# C717469.net
KiCad netlist of a schematic drawn in EAGLE
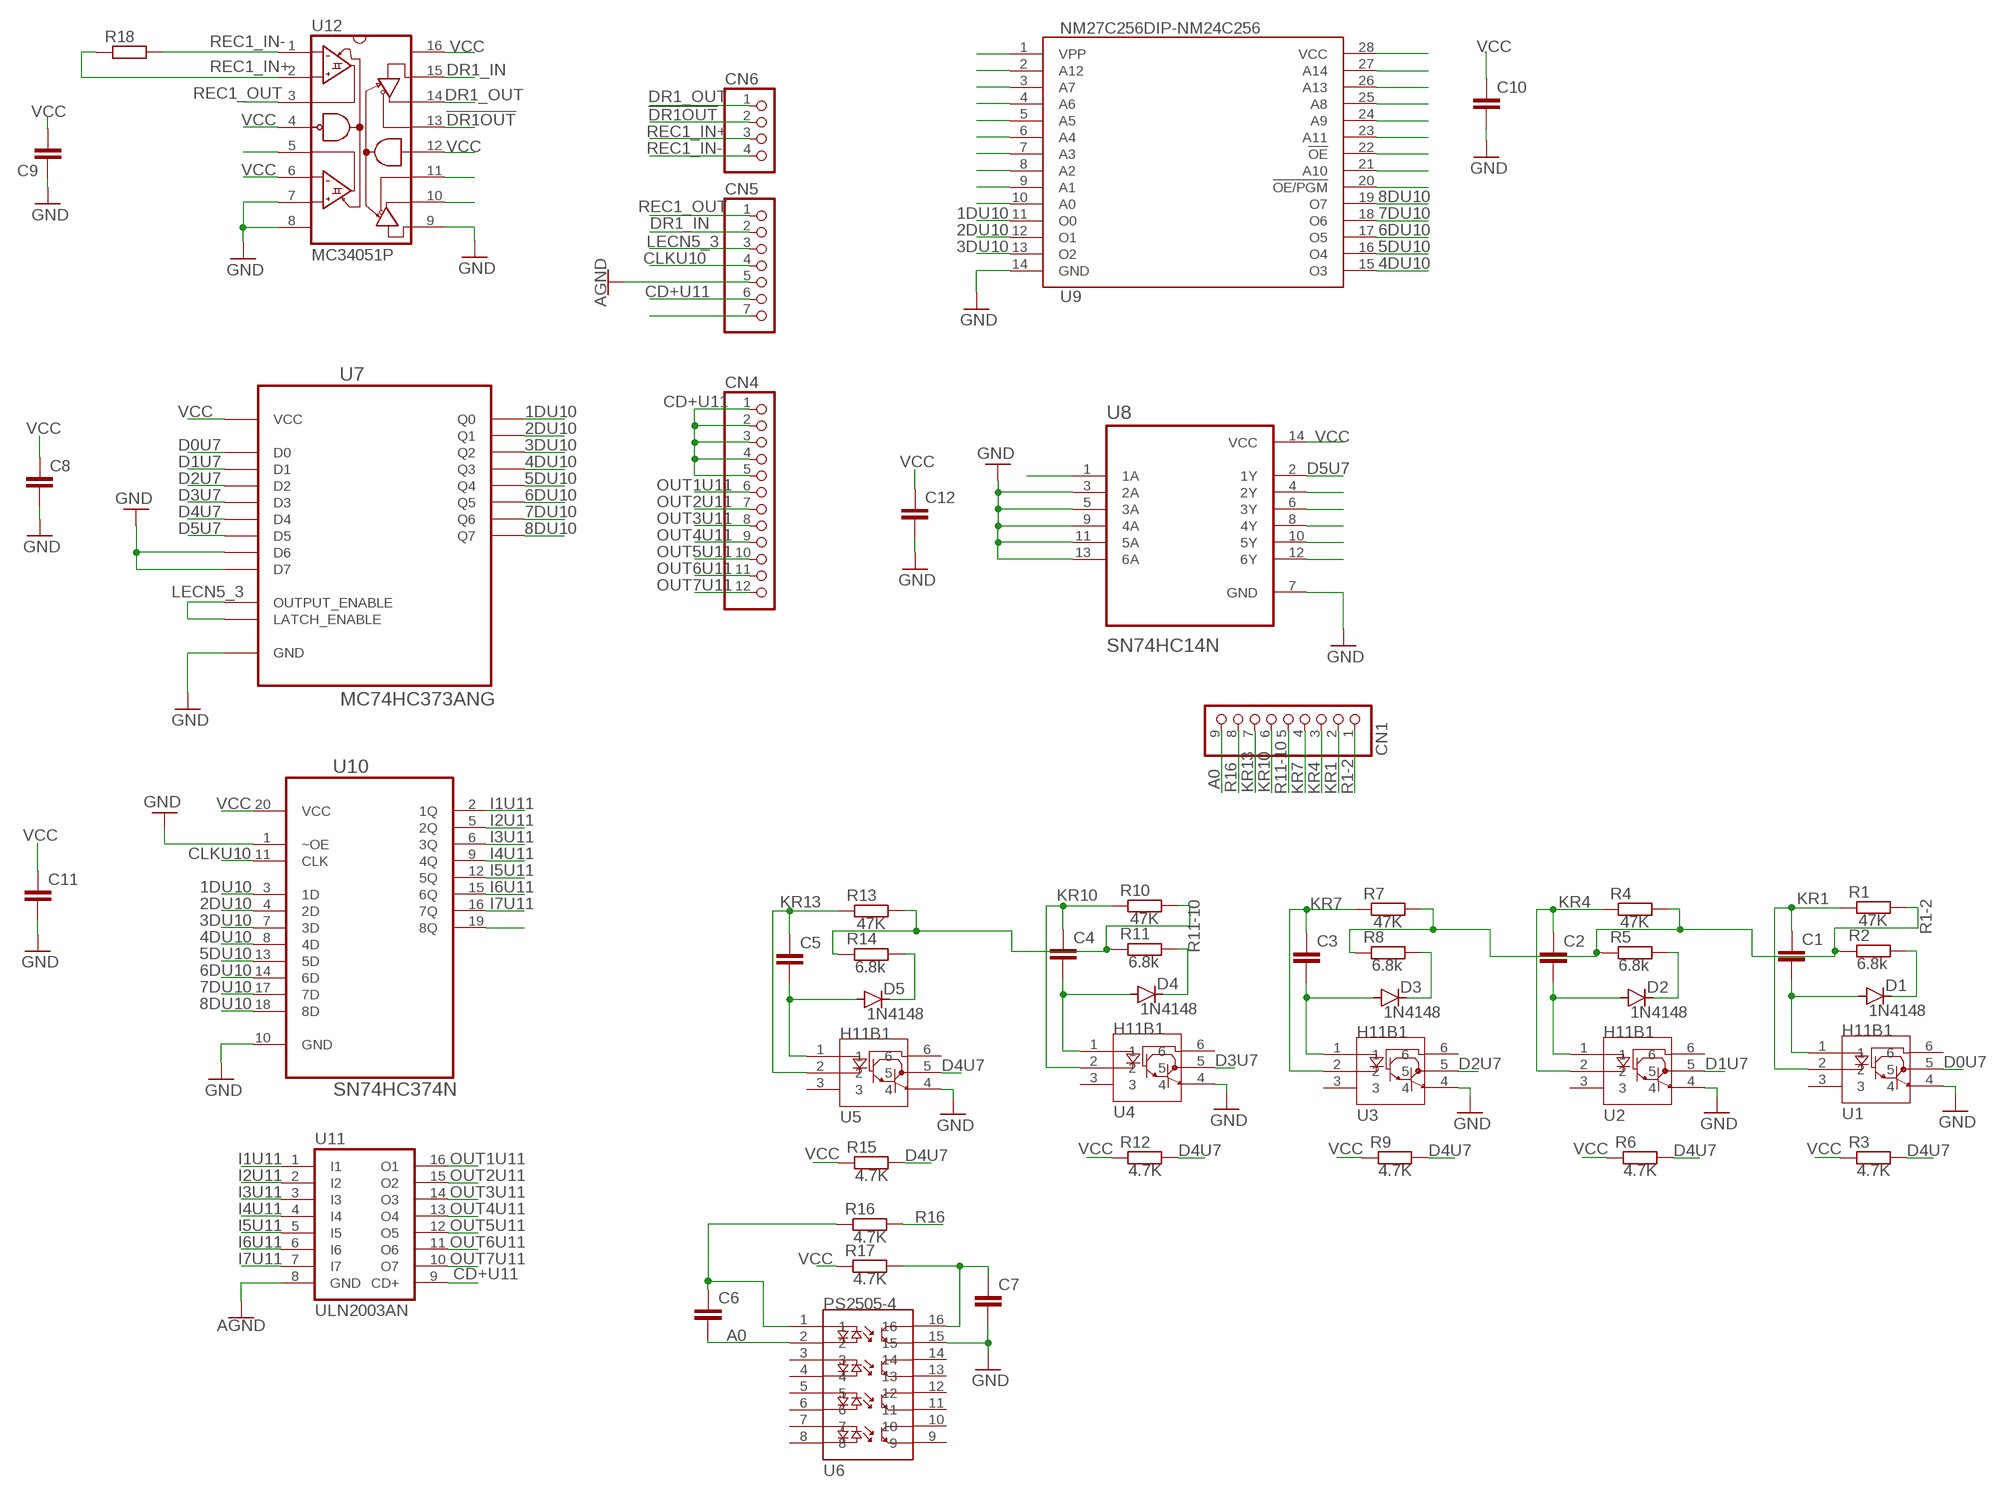
[diagram p0: schematic, sheet 1]

(export (version "E")
  (design (tool "Eeschema 10.0.6"))
  (components
    (comp (ref "C1")
      (value "C-EU025-025X050")
      (footprint "eagle-import:C025-025X050")
      (libsource (lib "eagle-import") (part "C-EU025-025X050"))
    )
    (comp (ref "C2")
      (value "C-EU025-025X050")
      (footprint "eagle-import:C025-025X050")
      (libsource (lib "eagle-import") (part "C-EU025-025X050"))
    )
    (comp (ref "C3")
      (value "C-EU025-025X050")
      (footprint "eagle-import:C025-025X050")
      (libsource (lib "eagle-import") (part "C-EU025-025X050"))
    )
    (comp (ref "C4")
      (value "C-EU025-025X050")
      (footprint "eagle-import:C025-025X050")
      (libsource (lib "eagle-import") (part "C-EU025-025X050"))
    )
    (comp (ref "C5")
      (value "C-EU025-025X050")
      (footprint "eagle-import:C025-025X050")
      (libsource (lib "eagle-import") (part "C-EU025-025X050"))
    )
    (comp (ref "C6")
      (value "C-EU025-025X050")
      (footprint "eagle-import:C025-025X050")
      (libsource (lib "eagle-import") (part "C-EU025-025X050"))
    )
    (comp (ref "C7")
      (value "C-EU025-025X050")
      (footprint "eagle-import:C025-025X050")
      (libsource (lib "eagle-import") (part "C-EU025-025X050"))
    )
    (comp (ref "C8")
      (value "C-EU025-025X050")
      (footprint "eagle-import:C025-025X050")
      (libsource (lib "eagle-import") (part "C-EU025-025X050"))
    )
    (comp (ref "C9")
      (value "C-EU025-025X050")
      (footprint "eagle-import:C025-025X050")
      (libsource (lib "eagle-import") (part "C-EU025-025X050"))
    )
    (comp (ref "C10")
      (value "C-EU025-025X050")
      (footprint "eagle-import:C025-025X050")
      (libsource (lib "eagle-import") (part "C-EU025-025X050"))
    )
    (comp (ref "C11")
      (value "C-EU025-025X050")
      (footprint "eagle-import:C025-025X050")
      (libsource (lib "eagle-import") (part "C-EU025-025X050"))
    )
    (comp (ref "C12")
      (value "C-EU025-025X050")
      (footprint "eagle-import:C025-025X050")
      (libsource (lib "eagle-import") (part "C-EU025-025X050"))
    )
    (comp (ref "CN1")
      (value "PINHD-1X9")
      (footprint "eagle-import:1X09")
      (libsource (lib "eagle-import") (part "PINHD-1X9"))
    )
    (comp (ref "CN4")
      (value "PINHD-1X12")
      (footprint "eagle-import:1X12")
      (libsource (lib "eagle-import") (part "PINHD-1X12"))
    )
    (comp (ref "CN5")
      (value "PINHD-1X7")
      (footprint "eagle-import:1X07")
      (libsource (lib "eagle-import") (part "PINHD-1X7"))
    )
    (comp (ref "CN6")
      (value "PINHD-1X4")
      (footprint "eagle-import:1X04")
      (libsource (lib "eagle-import") (part "PINHD-1X4"))
    )
    (comp (ref "D1")
      (value "1N4148")
      (footprint "eagle-import:DO35-10")
      (libsource (lib "eagle-import") (part "1N4148DO35-10"))
    )
    (comp (ref "D2")
      (value "1N4148")
      (footprint "eagle-import:DO35-10")
      (libsource (lib "eagle-import") (part "1N4148DO35-10"))
    )
    (comp (ref "D3")
      (value "1N4148")
      (footprint "eagle-import:DO35-10")
      (libsource (lib "eagle-import") (part "1N4148DO35-10"))
    )
    (comp (ref "D4")
      (value "1N4148")
      (footprint "eagle-import:DO35-10")
      (libsource (lib "eagle-import") (part "1N4148DO35-10"))
    )
    (comp (ref "D5")
      (value "1N4148")
      (footprint "eagle-import:DO35-10")
      (libsource (lib "eagle-import") (part "1N4148DO35-10"))
    )
    (comp (ref "R1")
      (value "47K")
      (footprint "eagle-import:0207_10")
      (libsource (lib "eagle-import") (part "R-EU_0207/10"))
    )
    (comp (ref "R2")
      (value "6.8k")
      (footprint "eagle-import:0207_10")
      (libsource (lib "eagle-import") (part "R-EU_0207/10"))
    )
    (comp (ref "R3")
      (value "4.7K")
      (footprint "eagle-import:0207_10")
      (libsource (lib "eagle-import") (part "R-EU_0207/10"))
    )
    (comp (ref "R4")
      (value "47K")
      (footprint "eagle-import:0207_10")
      (libsource (lib "eagle-import") (part "R-EU_0207/10"))
    )
    (comp (ref "R5")
      (value "6.8k")
      (footprint "eagle-import:0207_10")
      (libsource (lib "eagle-import") (part "R-EU_0207/10"))
    )
    (comp (ref "R6")
      (value "4.7K")
      (footprint "eagle-import:0207_10")
      (libsource (lib "eagle-import") (part "R-EU_0207/10"))
    )
    (comp (ref "R7")
      (value "47K")
      (footprint "eagle-import:0207_10")
      (libsource (lib "eagle-import") (part "R-EU_0207/10"))
    )
    (comp (ref "R8")
      (value "6.8k")
      (footprint "eagle-import:0207_10")
      (libsource (lib "eagle-import") (part "R-EU_0207/10"))
    )
    (comp (ref "R9")
      (value "4.7K")
      (footprint "eagle-import:0207_10")
      (libsource (lib "eagle-import") (part "R-EU_0207/10"))
    )
    (comp (ref "R10")
      (value "47K")
      (footprint "eagle-import:0207_10")
      (libsource (lib "eagle-import") (part "R-EU_0207/10"))
    )
    (comp (ref "R11")
      (value "6.8k")
      (footprint "eagle-import:0207_10")
      (libsource (lib "eagle-import") (part "R-EU_0207/10"))
    )
    (comp (ref "R12")
      (value "4.7K")
      (footprint "eagle-import:0207_10")
      (libsource (lib "eagle-import") (part "R-EU_0207/10"))
    )
    (comp (ref "R13")
      (value "47K")
      (footprint "eagle-import:0207_10")
      (libsource (lib "eagle-import") (part "R-EU_0207/10"))
    )
    (comp (ref "R14")
      (value "6.8k")
      (footprint "eagle-import:0207_10")
      (libsource (lib "eagle-import") (part "R-EU_0207/10"))
    )
    (comp (ref "R15")
      (value "4.7K")
      (footprint "eagle-import:0207_10")
      (libsource (lib "eagle-import") (part "R-EU_0207/10"))
    )
    (comp (ref "R16")
      (value "4.7K")
      (footprint "eagle-import:0207_10")
      (libsource (lib "eagle-import") (part "R-EU_0207/10"))
    )
    (comp (ref "R17")
      (value "4.7K")
      (footprint "eagle-import:0207_10")
      (libsource (lib "eagle-import") (part "R-EU_0207/10"))
    )
    (comp (ref "R18")
      (value "R-EU_0207/10")
      (footprint "eagle-import:0207_10")
      (libsource (lib "eagle-import") (part "R-EU_0207/10"))
    )
    (comp (ref "U1")
      (value "H11B1")
      (footprint "eagle-import:DIP762W50P254L730H410Q6")
      (libsource (lib "eagle-import") (part "H11B1DIP6"))
    )
    (comp (ref "U2")
      (value "H11B1")
      (footprint "eagle-import:DIP762W50P254L730H410Q6")
      (libsource (lib "eagle-import") (part "H11B1DIP6"))
    )
    (comp (ref "U3")
      (value "H11B1")
      (footprint "eagle-import:DIP762W50P254L730H410Q6")
      (libsource (lib "eagle-import") (part "H11B1DIP6"))
    )
    (comp (ref "U4")
      (value "H11B1")
      (footprint "eagle-import:DIP762W50P254L730H410Q6")
      (libsource (lib "eagle-import") (part "H11B1DIP6"))
    )
    (comp (ref "U5")
      (value "H11B1")
      (footprint "eagle-import:DIP762W50P254L730H410Q6")
      (libsource (lib "eagle-import") (part "H11B1DIP6"))
    )
    (comp (ref "U6")
      (value "PS2505-4")
      (footprint "eagle-import:D16-L")
      (libsource (lib "eagle-import") (part "PS2505-4"))
    )
    (comp (ref "U7")
      (value "MC74HC373ANG")
      (footprint "eagle-import:DIP254P762X457-20")
      (fields (field (name "MF") "ON Semiconductor"))
      (libsource (lib "eagle-import") (part "MC74HC373ANG"))
    )
    (comp (ref "U8")
      (value "SN74HC14N")
      (footprint "eagle-import:DIP794W45P254L1969H508Q14")
      (fields (field (name "MF") "Texas Instruments"))
      (libsource (lib "eagle-import") (part "SN74HC14N"))
    )
    (comp (ref "U9")
      (value "NM27C256DIP-NM24C256")
      (footprint "eagle-import:DIP1499W48P254L3734H572Q28")
      (libsource (lib "eagle-import") (part "NM27C256DIP-NM24C256"))
    )
    (comp (ref "U10")
      (value "SN74HC374N")
      (footprint "eagle-import:DIP254P762X508-20")
      (fields (field (name "MF") "Texas Instruments"))
      (libsource (lib "eagle-import") (part "SN74HC374N"))
    )
    (comp (ref "U11")
      (value "ULN2003AN")
      (footprint "eagle-import:DIL16")
      (libsource (lib "eagle-import") (part "ULN2003AN"))
    )
    (comp (ref "U12")
      (value "MC34051P")
      (footprint "eagle-import:D16")
      (libsource (lib "eagle-import") (part "MC34051P"))
    )
  )
  (nets
    (net (code "1") (name "/1DU10") (class "Default")
      (node (ref "U10") (pin "3") (pinfunction "1D_3") (pintype "input"))
      (node (ref "U7") (pin "2") (pinfunction "Q0_2") (pintype "output"))
      (node (ref "U9") (pin "11") (pinfunction "O0_11") (pintype "bidirectional"))
    )
    (net (code "2") (name "/2DU10") (class "Default")
      (node (ref "U10") (pin "4") (pinfunction "2D_4") (pintype "input"))
      (node (ref "U7") (pin "5") (pinfunction "Q1_5") (pintype "output"))
      (node (ref "U9") (pin "12") (pinfunction "O1_12") (pintype "bidirectional"))
    )
    (net (code "3") (name "/3DU10") (class "Default")
      (node (ref "U10") (pin "7") (pinfunction "3D_7") (pintype "input"))
      (node (ref "U7") (pin "6") (pinfunction "Q2_6") (pintype "output"))
      (node (ref "U9") (pin "13") (pinfunction "O2_13") (pintype "bidirectional"))
    )
    (net (code "4") (name "/4DU10") (class "Default")
      (node (ref "U10") (pin "8") (pinfunction "4D_8") (pintype "input"))
      (node (ref "U7") (pin "9") (pinfunction "Q3_9") (pintype "output"))
      (node (ref "U9") (pin "15") (pinfunction "O3_15") (pintype "bidirectional"))
    )
    (net (code "5") (name "/5DU10") (class "Default")
      (node (ref "U10") (pin "13") (pinfunction "5D_13") (pintype "input"))
      (node (ref "U7") (pin "12") (pinfunction "Q4_12") (pintype "output"))
      (node (ref "U9") (pin "16") (pinfunction "O4_16") (pintype "bidirectional"))
    )
    (net (code "6") (name "/6DU10") (class "Default")
      (node (ref "U10") (pin "14") (pinfunction "6D_14") (pintype "input"))
      (node (ref "U7") (pin "15") (pinfunction "Q5_15") (pintype "output"))
      (node (ref "U9") (pin "17") (pinfunction "O5_17") (pintype "bidirectional"))
    )
    (net (code "7") (name "/7DU10") (class "Default")
      (node (ref "U10") (pin "17") (pinfunction "7D_17") (pintype "input"))
      (node (ref "U7") (pin "16") (pinfunction "Q6_16") (pintype "output"))
      (node (ref "U9") (pin "18") (pinfunction "O6_18") (pintype "bidirectional"))
    )
    (net (code "8") (name "/8DU10") (class "Default")
      (node (ref "U10") (pin "18") (pinfunction "8D_18") (pintype "input"))
      (node (ref "U7") (pin "19") (pinfunction "Q7_19") (pintype "output"))
      (node (ref "U9") (pin "19") (pinfunction "O7_19") (pintype "bidirectional"))
    )
    (net (code "9") (name "/A0") (class "Default")
      (node (ref "C6") (pin "2") (pinfunction "2_2") (pintype "passive"))
      (node (ref "CN1") (pin "9") (pinfunction "9_9") (pintype "passive"))
      (node (ref "U6") (pin "2") (pinfunction "2_2") (pintype "bidirectional"))
    )
    (net (code "10") (name "/CD+U11") (class "Default")
      (node (ref "CN4") (pin "1") (pinfunction "1_1") (pintype "passive"))
      (node (ref "CN4") (pin "2") (pinfunction "2_2") (pintype "passive"))
      (node (ref "CN4") (pin "3") (pinfunction "3_3") (pintype "passive"))
      (node (ref "CN4") (pin "4") (pinfunction "4_4") (pintype "passive"))
      (node (ref "CN4") (pin "5") (pinfunction "5_5") (pintype "passive"))
      (node (ref "CN5") (pin "6") (pinfunction "6_6") (pintype "passive"))
      (node (ref "U11") (pin "9") (pinfunction "CD+_9") (pintype "passive"))
    )
    (net (code "11") (name "/CLKU10") (class "Default")
      (node (ref "CN5") (pin "4") (pinfunction "4_4") (pintype "passive"))
      (node (ref "U10") (pin "11") (pinfunction "CLK_11") (pintype "input"))
    )
    (net (code "12") (name "/D0U7") (class "Default")
      (node (ref "U1") (pin "5") (pinfunction "5_5") (pintype "bidirectional"))
      (node (ref "U7") (pin "3") (pinfunction "D0_3") (pintype "input"))
    )
    (net (code "13") (name "/D1U7") (class "Default")
      (node (ref "U2") (pin "5") (pinfunction "5_5") (pintype "bidirectional"))
      (node (ref "U7") (pin "4") (pinfunction "D1_4") (pintype "input"))
    )
    (net (code "14") (name "/D2U7") (class "Default")
      (node (ref "U3") (pin "5") (pinfunction "5_5") (pintype "bidirectional"))
      (node (ref "U7") (pin "7") (pinfunction "D2_7") (pintype "input"))
    )
    (net (code "15") (name "/D3U7") (class "Default")
      (node (ref "U4") (pin "5") (pinfunction "5_5") (pintype "bidirectional"))
      (node (ref "U7") (pin "8") (pinfunction "D3_8") (pintype "input"))
    )
    (net (code "16") (name "/D4U7") (class "Default")
      (node (ref "R12") (pin "2") (pinfunction "2_2") (pintype "passive"))
      (node (ref "R15") (pin "2") (pinfunction "2_2") (pintype "passive"))
      (node (ref "R3") (pin "2") (pinfunction "2_2") (pintype "passive"))
      (node (ref "R6") (pin "2") (pinfunction "2_2") (pintype "passive"))
      (node (ref "R9") (pin "2") (pinfunction "2_2") (pintype "passive"))
      (node (ref "U5") (pin "5") (pinfunction "5_5") (pintype "bidirectional"))
      (node (ref "U7") (pin "13") (pinfunction "D4_13") (pintype "input"))
    )
    (net (code "17") (name "/D5U7") (class "Default")
      (node (ref "U7") (pin "14") (pinfunction "D5_14") (pintype "input"))
      (node (ref "U8") (pin "2") (pinfunction "1Y_2") (pintype "output"))
    )
    (net (code "18") (name "/DR1_IN") (class "Default")
      (node (ref "CN5") (pin "2") (pinfunction "2_2") (pintype "passive"))
      (node (ref "U12") (pin "15") (pinfunction "DR1IN_15") (pintype "bidirectional"))
    )
    (net (code "19") (name "/DR1_OUT") (class "Default")
      (node (ref "CN6") (pin "1") (pinfunction "1_1") (pintype "passive"))
      (node (ref "U12") (pin "14") (pinfunction "DR1OUT_14") (pintype "bidirectional"))
    )
    (net (code "20") (name "/I1U11") (class "Default")
      (node (ref "U10") (pin "2") (pinfunction "1Q_2") (pintype "output"))
      (node (ref "U11") (pin "1") (pinfunction "I1_1") (pintype "input"))
    )
    (net (code "21") (name "/I2U11") (class "Default")
      (node (ref "U10") (pin "5") (pinfunction "2Q_5") (pintype "output"))
      (node (ref "U11") (pin "2") (pinfunction "I2_2") (pintype "input"))
    )
    (net (code "22") (name "/I3U11") (class "Default")
      (node (ref "U10") (pin "6") (pinfunction "3Q_6") (pintype "output"))
      (node (ref "U11") (pin "3") (pinfunction "I3_3") (pintype "input"))
    )
    (net (code "23") (name "/I4U11") (class "Default")
      (node (ref "U10") (pin "9") (pinfunction "4Q_9") (pintype "output"))
      (node (ref "U11") (pin "4") (pinfunction "I4_4") (pintype "input"))
    )
    (net (code "24") (name "/I5U11") (class "Default")
      (node (ref "U10") (pin "12") (pinfunction "5Q_12") (pintype "output"))
      (node (ref "U11") (pin "5") (pinfunction "I5_5") (pintype "input"))
    )
    (net (code "25") (name "/I6U11") (class "Default")
      (node (ref "U10") (pin "15") (pinfunction "6Q_15") (pintype "output"))
      (node (ref "U11") (pin "6") (pinfunction "I6_6") (pintype "input"))
    )
    (net (code "26") (name "/I7U11") (class "Default")
      (node (ref "U10") (pin "16") (pinfunction "7Q_16") (pintype "output"))
      (node (ref "U11") (pin "7") (pinfunction "I7_7") (pintype "input"))
    )
    (net (code "27") (name "/KR1") (class "Default")
      (node (ref "C1") (pin "1") (pinfunction "1_1") (pintype "passive"))
      (node (ref "CN1") (pin "2") (pinfunction "2_2") (pintype "passive"))
      (node (ref "R1") (pin "1") (pinfunction "1_1") (pintype "passive"))
      (node (ref "U1") (pin "2") (pinfunction "2_2") (pintype "bidirectional"))
    )
    (net (code "28") (name "/KR4") (class "Default")
      (node (ref "C2") (pin "1") (pinfunction "1_1") (pintype "passive"))
      (node (ref "CN1") (pin "3") (pinfunction "3_3") (pintype "passive"))
      (node (ref "R4") (pin "1") (pinfunction "1_1") (pintype "passive"))
      (node (ref "U2") (pin "2") (pinfunction "2_2") (pintype "bidirectional"))
    )
    (net (code "29") (name "/KR7") (class "Default")
      (node (ref "C3") (pin "1") (pinfunction "1_1") (pintype "passive"))
      (node (ref "CN1") (pin "4") (pinfunction "4_4") (pintype "passive"))
      (node (ref "R7") (pin "1") (pinfunction "1_1") (pintype "passive"))
      (node (ref "U3") (pin "2") (pinfunction "2_2") (pintype "bidirectional"))
    )
    (net (code "30") (name "/KR10") (class "Default")
      (node (ref "C4") (pin "1") (pinfunction "1_1") (pintype "passive"))
      (node (ref "CN1") (pin "6") (pinfunction "6_6") (pintype "passive"))
      (node (ref "R10") (pin "1") (pinfunction "1_1") (pintype "passive"))
      (node (ref "U4") (pin "2") (pinfunction "2_2") (pintype "bidirectional"))
    )
    (net (code "31") (name "/KR13") (class "Default")
      (node (ref "C5") (pin "1") (pinfunction "1_1") (pintype "passive"))
      (node (ref "CN1") (pin "7") (pinfunction "7_7") (pintype "passive"))
      (node (ref "R13") (pin "1") (pinfunction "1_1") (pintype "passive"))
      (node (ref "U5") (pin "2") (pinfunction "2_2") (pintype "bidirectional"))
    )
    (net (code "32") (name "/LECN5_3") (class "Default")
      (node (ref "CN5") (pin "3") (pinfunction "3_3") (pintype "passive"))
      (node (ref "U7") (pin "1") (pinfunction "OUTPUT_ENABLE_1") (pintype "input"))
      (node (ref "U7") (pin "11") (pinfunction "LATCH_ENABLE_11") (pintype "input"))
    )
    (net (code "33") (name "/OUT1U11") (class "Default")
      (node (ref "CN4") (pin "6") (pinfunction "6_6") (pintype "passive"))
      (node (ref "U11") (pin "16") (pinfunction "O1_16") (pintype "open_collector"))
    )
    (net (code "34") (name "/OUT2U11") (class "Default")
      (node (ref "CN4") (pin "7") (pinfunction "7_7") (pintype "passive"))
      (node (ref "U11") (pin "15") (pinfunction "O2_15") (pintype "open_collector"))
    )
    (net (code "35") (name "/OUT3U11") (class "Default")
      (node (ref "CN4") (pin "8") (pinfunction "8_8") (pintype "passive"))
      (node (ref "U11") (pin "14") (pinfunction "O3_14") (pintype "open_collector"))
    )
    (net (code "36") (name "/OUT4U11") (class "Default")
      (node (ref "CN4") (pin "9") (pinfunction "9_9") (pintype "passive"))
      (node (ref "U11") (pin "13") (pinfunction "O4_13") (pintype "open_collector"))
    )
    (net (code "37") (name "/OUT5U11") (class "Default")
      (node (ref "CN4") (pin "10") (pinfunction "10_10") (pintype "passive"))
      (node (ref "U11") (pin "12") (pinfunction "O5_12") (pintype "open_collector"))
    )
    (net (code "38") (name "/OUT6U11") (class "Default")
      (node (ref "CN4") (pin "11") (pinfunction "11_11") (pintype "passive"))
      (node (ref "U11") (pin "11") (pinfunction "O6_11") (pintype "open_collector"))
    )
    (net (code "39") (name "/OUT7U11") (class "Default")
      (node (ref "CN4") (pin "12") (pinfunction "12_12") (pintype "passive"))
      (node (ref "U11") (pin "10") (pinfunction "O7_10") (pintype "open_collector"))
    )
    (net (code "40") (name "/R1-2") (class "Default")
      (node (ref "CN1") (pin "1") (pinfunction "1_1") (pintype "passive"))
      (node (ref "R1") (pin "2") (pinfunction "2_2") (pintype "passive"))
      (node (ref "R2") (pin "1") (pinfunction "1_1") (pintype "passive"))
      (node (ref "R4") (pin "2") (pinfunction "2_2") (pintype "passive"))
      (node (ref "R5") (pin "1") (pinfunction "1_1") (pintype "passive"))
      (node (ref "R7") (pin "2") (pinfunction "2_2") (pintype "passive"))
      (node (ref "R8") (pin "1") (pinfunction "1_1") (pintype "passive"))
    )
    (net (code "41") (name "/R11-10") (class "Default")
      (node (ref "CN1") (pin "5") (pinfunction "5_5") (pintype "passive"))
      (node (ref "R10") (pin "2") (pinfunction "2_2") (pintype "passive"))
      (node (ref "R11") (pin "1") (pinfunction "1_1") (pintype "passive"))
      (node (ref "R13") (pin "2") (pinfunction "2_2") (pintype "passive"))
      (node (ref "R14") (pin "1") (pinfunction "1_1") (pintype "passive"))
    )
    (net (code "42") (name "/R16") (class "Default")
      (node (ref "CN1") (pin "8") (pinfunction "8_8") (pintype "passive"))
      (node (ref "R16") (pin "2") (pinfunction "2_2") (pintype "passive"))
    )
    (net (code "43") (name "/REC1_IN+") (class "Default")
      (node (ref "CN6") (pin "3") (pinfunction "3_3") (pintype "passive"))
      (node (ref "R18") (pin "1") (pinfunction "1_1") (pintype "passive"))
      (node (ref "U12") (pin "2") (pinfunction "REC1+IN_2") (pintype "bidirectional"))
    )
    (net (code "44") (name "/REC1_IN-") (class "Default")
      (node (ref "CN6") (pin "4") (pinfunction "4_4") (pintype "passive"))
      (node (ref "R18") (pin "2") (pinfunction "2_2") (pintype "passive"))
      (node (ref "U12") (pin "1") (pinfunction "REC1-IN_1") (pintype "bidirectional"))
    )
    (net (code "45") (name "/REC1_OUT") (class "Default")
      (node (ref "CN5") (pin "1") (pinfunction "1_1") (pintype "passive"))
      (node (ref "U12") (pin "3") (pinfunction "REC1OUT_3") (pintype "bidirectional"))
    )
    (net (code "46") (name "/VCC") (class "Default")
      (node (ref "C10") (pin "1") (pinfunction "1_1") (pintype "passive"))
      (node (ref "C11") (pin "1") (pinfunction "1_1") (pintype "passive"))
      (node (ref "C12") (pin "1") (pinfunction "1_1") (pintype "passive"))
      (node (ref "C8") (pin "1") (pinfunction "1_1") (pintype "passive"))
      (node (ref "C9") (pin "2") (pinfunction "2_2") (pintype "passive"))
      (node (ref "R12") (pin "1") (pinfunction "1_1") (pintype "passive"))
      (node (ref "R15") (pin "1") (pinfunction "1_1") (pintype "passive"))
      (node (ref "R17") (pin "1") (pinfunction "1_1") (pintype "passive"))
      (node (ref "R3") (pin "1") (pinfunction "1_1") (pintype "passive"))
      (node (ref "R6") (pin "1") (pinfunction "1_1") (pintype "passive"))
      (node (ref "R9") (pin "1") (pinfunction "1_1") (pintype "passive"))
      (node (ref "U10") (pin "20") (pinfunction "VCC_20") (pintype "power_in"))
      (node (ref "U12") (pin "12") (pinfunction "DREN_12") (pintype "bidirectional"))
      (node (ref "U12") (pin "16") (pinfunction "VCC_16") (pintype "bidirectional"))
      (node (ref "U12") (pin "4") (pinfunction "~{RECEN}_4") (pintype "bidirectional"))
      (node (ref "U12") (pin "6") (pinfunction "REC2+IN_6") (pintype "bidirectional"))
      (node (ref "U7") (pin "20") (pinfunction "VCC_20") (pintype "power_in"))
      (node (ref "U8") (pin "14") (pinfunction "VCC_14") (pintype "power_in"))
    )
    (net (code "47") (name "/~{DR1OUT}") (class "Default")
      (node (ref "CN6") (pin "2") (pinfunction "2_2") (pintype "passive"))
      (node (ref "U12") (pin "13") (pinfunction "~{DR1OUT}_13") (pintype "bidirectional"))
    )
    (net (code "48") (name "AGND") (class "Default")
      (node (ref "CN5") (pin "5") (pinfunction "5_5") (pintype "passive"))
      (node (ref "U11") (pin "8") (pinfunction "GND_8") (pintype "power_in"))
    )
    (net (code "49") (name "GND") (class "Default")
      (node (ref "C10") (pin "2") (pinfunction "2_2") (pintype "passive"))
      (node (ref "C11") (pin "2") (pinfunction "2_2") (pintype "passive"))
      (node (ref "C12") (pin "2") (pinfunction "2_2") (pintype "passive"))
      (node (ref "C7") (pin "2") (pinfunction "2_2") (pintype "passive"))
      (node (ref "C8") (pin "2") (pinfunction "2_2") (pintype "passive"))
      (node (ref "C9") (pin "1") (pinfunction "1_1") (pintype "passive"))
      (node (ref "U1") (pin "4") (pinfunction "4_4") (pintype "bidirectional"))
      (node (ref "U10") (pin "1") (pinfunction "~{OE}_1") (pintype "input"))
      (node (ref "U10") (pin "10") (pinfunction "GND_10") (pintype "passive"))
      (node (ref "U12") (pin "7") (pinfunction "REC2-IN_7") (pintype "bidirectional"))
      (node (ref "U12") (pin "8") (pinfunction "GND_8") (pintype "bidirectional"))
      (node (ref "U12") (pin "9") (pinfunction "DR2IN_9") (pintype "bidirectional"))
      (node (ref "U2") (pin "4") (pinfunction "4_4") (pintype "bidirectional"))
      (node (ref "U3") (pin "4") (pinfunction "4_4") (pintype "bidirectional"))
      (node (ref "U4") (pin "4") (pinfunction "4_4") (pintype "bidirectional"))
      (node (ref "U5") (pin "4") (pinfunction "4_4") (pintype "bidirectional"))
      (node (ref "U6") (pin "15") (pinfunction "15_15") (pintype "bidirectional"))
      (node (ref "U7") (pin "10") (pinfunction "GND_10") (pintype "passive"))
      (node (ref "U7") (pin "17") (pinfunction "D6_17") (pintype "input"))
      (node (ref "U7") (pin "18") (pinfunction "D7_18") (pintype "input"))
      (node (ref "U8") (pin "11") (pinfunction "5A_11") (pintype "input"))
      (node (ref "U8") (pin "13") (pinfunction "6A_13") (pintype "input"))
      (node (ref "U8") (pin "3") (pinfunction "2A_3") (pintype "input"))
      (node (ref "U8") (pin "5") (pinfunction "3A_5") (pintype "input"))
      (node (ref "U8") (pin "7") (pinfunction "GND_7") (pintype "power_in"))
      (node (ref "U8") (pin "9") (pinfunction "4A_9") (pintype "input"))
      (node (ref "U9") (pin "14") (pinfunction "GND_14") (pintype "bidirectional"))
    )
    (net (code "50") (name "Net-(C1-Pad2)") (class "Default")
      (node (ref "C1") (pin "2") (pinfunction "2_2") (pintype "passive"))
      (node (ref "D1") (pin "A") (pinfunction "A_A") (pintype "passive"))
      (node (ref "U1") (pin "1") (pinfunction "1_1") (pintype "bidirectional"))
    )
    (net (code "51") (name "Net-(C2-Pad2)") (class "Default")
      (node (ref "C2") (pin "2") (pinfunction "2_2") (pintype "passive"))
      (node (ref "D2") (pin "A") (pinfunction "A_A") (pintype "passive"))
      (node (ref "U2") (pin "1") (pinfunction "1_1") (pintype "bidirectional"))
    )
    (net (code "52") (name "Net-(C3-Pad2)") (class "Default")
      (node (ref "C3") (pin "2") (pinfunction "2_2") (pintype "passive"))
      (node (ref "D3") (pin "A") (pinfunction "A_A") (pintype "passive"))
      (node (ref "U3") (pin "1") (pinfunction "1_1") (pintype "bidirectional"))
    )
    (net (code "53") (name "Net-(C4-Pad2)") (class "Default")
      (node (ref "C4") (pin "2") (pinfunction "2_2") (pintype "passive"))
      (node (ref "D4") (pin "A") (pinfunction "A_A") (pintype "passive"))
      (node (ref "U4") (pin "1") (pinfunction "1_1") (pintype "bidirectional"))
    )
    (net (code "54") (name "Net-(C5-Pad2)") (class "Default")
      (node (ref "C5") (pin "2") (pinfunction "2_2") (pintype "passive"))
      (node (ref "D5") (pin "A") (pinfunction "A_A") (pintype "passive"))
      (node (ref "U5") (pin "1") (pinfunction "1_1") (pintype "bidirectional"))
    )
    (net (code "55") (name "Net-(C6-Pad1)") (class "Default")
      (node (ref "C6") (pin "1") (pinfunction "1_1") (pintype "passive"))
      (node (ref "R16") (pin "1") (pinfunction "1_1") (pintype "passive"))
      (node (ref "U6") (pin "1") (pinfunction "1_1") (pintype "bidirectional"))
    )
    (net (code "56") (name "Net-(C7-Pad1)") (class "Default")
      (node (ref "C7") (pin "1") (pinfunction "1_1") (pintype "passive"))
      (node (ref "R17") (pin "2") (pinfunction "2_2") (pintype "passive"))
      (node (ref "U6") (pin "16") (pinfunction "16_16") (pintype "bidirectional"))
    )
    (net (code "57") (name "Net-(D1-PadC)") (class "Default")
      (node (ref "D1") (pin "C") (pinfunction "C_C") (pintype "passive"))
      (node (ref "R2") (pin "2") (pinfunction "2_2") (pintype "passive"))
    )
    (net (code "58") (name "Net-(D2-PadC)") (class "Default")
      (node (ref "D2") (pin "C") (pinfunction "C_C") (pintype "passive"))
      (node (ref "R5") (pin "2") (pinfunction "2_2") (pintype "passive"))
    )
    (net (code "59") (name "Net-(D3-PadC)") (class "Default")
      (node (ref "D3") (pin "C") (pinfunction "C_C") (pintype "passive"))
      (node (ref "R8") (pin "2") (pinfunction "2_2") (pintype "passive"))
    )
    (net (code "60") (name "Net-(D4-PadC)") (class "Default")
      (node (ref "D4") (pin "C") (pinfunction "C_C") (pintype "passive"))
      (node (ref "R11") (pin "2") (pinfunction "2_2") (pintype "passive"))
    )
    (net (code "61") (name "Net-(D5-PadC)") (class "Default")
      (node (ref "D5") (pin "C") (pinfunction "C_C") (pintype "passive"))
      (node (ref "R14") (pin "2") (pinfunction "2_2") (pintype "passive"))
    )
    (net (code "62") (name "unconnected-(CN5-Pad7)") (class "Default")
      (node (ref "CN5") (pin "7") (pinfunction "7_7") (pintype "passive"))
    )
    (net (code "63") (name "unconnected-(U1-Pad3)") (class "Default")
      (node (ref "U1") (pin "3") (pinfunction "3_3") (pintype "bidirectional"))
    )
    (net (code "64") (name "unconnected-(U1-Pad6)") (class "Default")
      (node (ref "U1") (pin "6") (pinfunction "6_6") (pintype "bidirectional"))
    )
    (net (code "65") (name "unconnected-(U2-Pad3)") (class "Default")
      (node (ref "U2") (pin "3") (pinfunction "3_3") (pintype "bidirectional"))
    )
    (net (code "66") (name "unconnected-(U2-Pad6)") (class "Default")
      (node (ref "U2") (pin "6") (pinfunction "6_6") (pintype "bidirectional"))
    )
    (net (code "67") (name "unconnected-(U3-Pad3)") (class "Default")
      (node (ref "U3") (pin "3") (pinfunction "3_3") (pintype "bidirectional"))
    )
    (net (code "68") (name "unconnected-(U3-Pad6)") (class "Default")
      (node (ref "U3") (pin "6") (pinfunction "6_6") (pintype "bidirectional"))
    )
    (net (code "69") (name "unconnected-(U4-Pad3)") (class "Default")
      (node (ref "U4") (pin "3") (pinfunction "3_3") (pintype "bidirectional"))
    )
    (net (code "70") (name "unconnected-(U4-Pad6)") (class "Default")
      (node (ref "U4") (pin "6") (pinfunction "6_6") (pintype "bidirectional"))
    )
    (net (code "71") (name "unconnected-(U5-Pad3)") (class "Default")
      (node (ref "U5") (pin "3") (pinfunction "3_3") (pintype "bidirectional"))
    )
    (net (code "72") (name "unconnected-(U5-Pad6)") (class "Default")
      (node (ref "U5") (pin "6") (pinfunction "6_6") (pintype "bidirectional"))
    )
    (net (code "73") (name "unconnected-(U6-Pad3)") (class "Default")
      (node (ref "U6") (pin "3") (pinfunction "3_3") (pintype "bidirectional"))
    )
    (net (code "74") (name "unconnected-(U6-Pad4)") (class "Default")
      (node (ref "U6") (pin "4") (pinfunction "4_4") (pintype "bidirectional"))
    )
    (net (code "75") (name "unconnected-(U6-Pad5)") (class "Default")
      (node (ref "U6") (pin "5") (pinfunction "5_5") (pintype "bidirectional"))
    )
    (net (code "76") (name "unconnected-(U6-Pad6)") (class "Default")
      (node (ref "U6") (pin "6") (pinfunction "6_6") (pintype "bidirectional"))
    )
    (net (code "77") (name "unconnected-(U6-Pad7)") (class "Default")
      (node (ref "U6") (pin "7") (pinfunction "7_7") (pintype "bidirectional"))
    )
    (net (code "78") (name "unconnected-(U6-Pad8)") (class "Default")
      (node (ref "U6") (pin "8") (pinfunction "8_8") (pintype "bidirectional"))
    )
    (net (code "79") (name "unconnected-(U6-Pad9)") (class "Default")
      (node (ref "U6") (pin "9") (pinfunction "9_9") (pintype "bidirectional"))
    )
    (net (code "80") (name "unconnected-(U6-Pad10)") (class "Default")
      (node (ref "U6") (pin "10") (pinfunction "10_10") (pintype "bidirectional"))
    )
    (net (code "81") (name "unconnected-(U6-Pad11)") (class "Default")
      (node (ref "U6") (pin "11") (pinfunction "11_11") (pintype "bidirectional"))
    )
    (net (code "82") (name "unconnected-(U6-Pad12)") (class "Default")
      (node (ref "U6") (pin "12") (pinfunction "12_12") (pintype "bidirectional"))
    )
    (net (code "83") (name "unconnected-(U6-Pad13)") (class "Default")
      (node (ref "U6") (pin "13") (pinfunction "13_13") (pintype "bidirectional"))
    )
    (net (code "84") (name "unconnected-(U6-Pad14)") (class "Default")
      (node (ref "U6") (pin "14") (pinfunction "14_14") (pintype "bidirectional"))
    )
    (net (code "85") (name "unconnected-(U8-1A-Pad1)") (class "Default")
      (node (ref "U8") (pin "1") (pinfunction "1A_1") (pintype "input"))
    )
    (net (code "86") (name "unconnected-(U8-2Y-Pad4)") (class "Default")
      (node (ref "U8") (pin "4") (pinfunction "2Y_4") (pintype "output"))
    )
    (net (code "87") (name "unconnected-(U8-3Y-Pad6)") (class "Default")
      (node (ref "U8") (pin "6") (pinfunction "3Y_6") (pintype "output"))
    )
    (net (code "88") (name "unconnected-(U8-4Y-Pad8)") (class "Default")
      (node (ref "U8") (pin "8") (pinfunction "4Y_8") (pintype "output"))
    )
    (net (code "89") (name "unconnected-(U8-5Y-Pad10)") (class "Default")
      (node (ref "U8") (pin "10") (pinfunction "5Y_10") (pintype "output"))
    )
    (net (code "90") (name "unconnected-(U8-6Y-Pad12)") (class "Default")
      (node (ref "U8") (pin "12") (pinfunction "6Y_12") (pintype "output"))
    )
    (net (code "91") (name "unconnected-(U9-A0-Pad10)") (class "Default")
      (node (ref "U9") (pin "10") (pinfunction "A0_10") (pintype "bidirectional"))
    )
    (net (code "92") (name "unconnected-(U9-A1-Pad9)") (class "Default")
      (node (ref "U9") (pin "9") (pinfunction "A1_9") (pintype "bidirectional"))
    )
    (net (code "93") (name "unconnected-(U9-A2-Pad8)") (class "Default")
      (node (ref "U9") (pin "8") (pinfunction "A2_8") (pintype "bidirectional"))
    )
    (net (code "94") (name "unconnected-(U9-A3-Pad7)") (class "Default")
      (node (ref "U9") (pin "7") (pinfunction "A3_7") (pintype "bidirectional"))
    )
    (net (code "95") (name "unconnected-(U9-A4-Pad6)") (class "Default")
      (node (ref "U9") (pin "6") (pinfunction "A4_6") (pintype "bidirectional"))
    )
    (net (code "96") (name "unconnected-(U9-A5-Pad5)") (class "Default")
      (node (ref "U9") (pin "5") (pinfunction "A5_5") (pintype "bidirectional"))
    )
    (net (code "97") (name "unconnected-(U9-A6-Pad4)") (class "Default")
      (node (ref "U9") (pin "4") (pinfunction "A6_4") (pintype "bidirectional"))
    )
    (net (code "98") (name "unconnected-(U9-A7-Pad3)") (class "Default")
      (node (ref "U9") (pin "3") (pinfunction "A7_3") (pintype "bidirectional"))
    )
    (net (code "99") (name "unconnected-(U9-A8-Pad25)") (class "Default")
      (node (ref "U9") (pin "25") (pinfunction "A8_25") (pintype "bidirectional"))
    )
    (net (code "100") (name "unconnected-(U9-A9-Pad24)") (class "Default")
      (node (ref "U9") (pin "24") (pinfunction "A9_24") (pintype "bidirectional"))
    )
    (net (code "101") (name "unconnected-(U9-A10-Pad21)") (class "Default")
      (node (ref "U9") (pin "21") (pinfunction "A10_21") (pintype "bidirectional"))
    )
    (net (code "102") (name "unconnected-(U9-A11-Pad23)") (class "Default")
      (node (ref "U9") (pin "23") (pinfunction "A11_23") (pintype "bidirectional"))
    )
    (net (code "103") (name "unconnected-(U9-A12-Pad2)") (class "Default")
      (node (ref "U9") (pin "2") (pinfunction "A12_2") (pintype "bidirectional"))
    )
    (net (code "104") (name "unconnected-(U9-A13-Pad26)") (class "Default")
      (node (ref "U9") (pin "26") (pinfunction "A13_26") (pintype "bidirectional"))
    )
    (net (code "105") (name "unconnected-(U9-A14-Pad27)") (class "Default")
      (node (ref "U9") (pin "27") (pinfunction "A14_27") (pintype "bidirectional"))
    )
    (net (code "106") (name "unconnected-(U9-VCC-Pad28)") (class "Default")
      (node (ref "U9") (pin "28") (pinfunction "VCC_28") (pintype "bidirectional"))
    )
    (net (code "107") (name "unconnected-(U9-VPP-Pad1)") (class "Default")
      (node (ref "U9") (pin "1") (pinfunction "VPP_1") (pintype "bidirectional"))
    )
    (net (code "108") (name "unconnected-(U9-~{OE{slash}PGM}-Pad20)") (class "Default")
      (node (ref "U9") (pin "20") (pinfunction "~{OE/PGM}_20") (pintype "bidirectional"))
    )
    (net (code "109") (name "unconnected-(U9-~{OE}-Pad22)") (class "Default")
      (node (ref "U9") (pin "22") (pinfunction "~{OE}_22") (pintype "bidirectional"))
    )
    (net (code "110") (name "unconnected-(U10-8Q-Pad19)") (class "Default")
      (node (ref "U10") (pin "19") (pinfunction "8Q_19") (pintype "output"))
    )
    (net (code "111") (name "unconnected-(U12-DR2OUT-Pad10)") (class "Default")
      (node (ref "U12") (pin "10") (pinfunction "DR2OUT_10") (pintype "bidirectional"))
    )
    (net (code "112") (name "unconnected-(U12-REC2OUT-Pad5)") (class "Default")
      (node (ref "U12") (pin "5") (pinfunction "REC2OUT_5") (pintype "bidirectional"))
    )
    (net (code "113") (name "unconnected-(U12-~{DR2OUT}-Pad11)") (class "Default")
      (node (ref "U12") (pin "11") (pinfunction "~{DR2OUT}_11") (pintype "bidirectional"))
    )
  )
)
